# Power_InrushLimit.net
KiCad netlist of a schematic drawn in Altium Designer
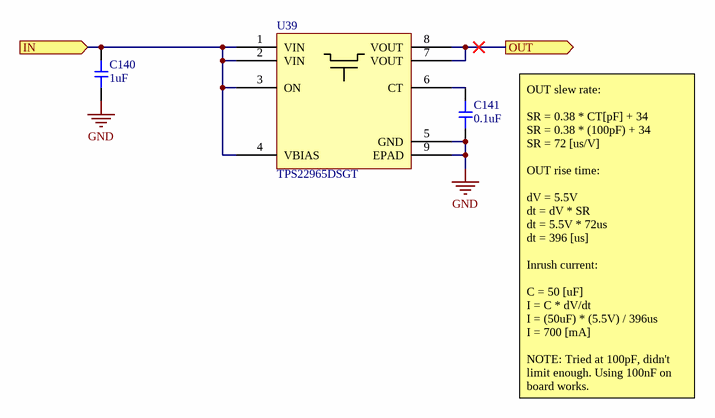
[diagram p0: Power_InrushLimit.SchDoc]

(export (version "E")
  (design (tool "Eeschema 10.0.6"))
  (components
    (comp (ref "C140")
      (value "1uF")
      (footprint "AMDC:0603-CAP")
      (description "Capacitor")
      (libsource (lib "AMDC") (part "Capacitor"))
    )
    (comp (ref "C141")
      (value "0.1uF")
      (footprint "AMDC:0603-CAP")
      (description "Capacitor")
      (libsource (lib "AMDC") (part "Capacitor"))
    )
    (comp (ref "U39")
      (value "TPS22965DSGT")
      (footprint "AMDC:SON50P200X80_HS-9N")
      (description "IC LOAD SWITCH 6A 8WSON")
      (libsource (lib "AMDC") (part "TPS22965DSGT"))
    )
  )
  (nets
    (net (code "1") (name "/IN") (class "Default")
      (node (ref "C140") (pin "2") (pinfunction "2_2") (pintype "passive"))
      (node (ref "U39") (pin "1") (pinfunction "VIN_1") (pintype "passive"))
      (node (ref "U39") (pin "2") (pinfunction "VIN_2") (pintype "passive"))
      (node (ref "U39") (pin "3") (pinfunction "ON_3") (pintype "passive"))
      (node (ref "U39") (pin "4") (pinfunction "VBIAS_4") (pintype "passive"))
    )
    (net (code "2") (name "/OUT") (class "Default")
      (node (ref "U39") (pin "7") (pinfunction "VOUT_7") (pintype "passive"))
      (node (ref "U39") (pin "8") (pinfunction "VOUT_8") (pintype "passive"))
    )
    (net (code "3") (name "GND") (class "Default")
      (node (ref "C140") (pin "1") (pinfunction "1_1") (pintype "passive"))
      (node (ref "C141") (pin "1") (pinfunction "1_1") (pintype "passive"))
      (node (ref "U39") (pin "5") (pinfunction "GND_5") (pintype "passive"))
      (node (ref "U39") (pin "9") (pinfunction "EPAD_9") (pintype "passive"))
    )
    (net (code "4") (name "Net-(U39-CT)") (class "Default")
      (node (ref "C141") (pin "2") (pinfunction "2_2") (pintype "passive"))
      (node (ref "U39") (pin "6") (pinfunction "CT_6") (pintype "passive"))
    )
  )
)
